# Power.net
KiCad netlist of a schematic drawn in Altium Designer
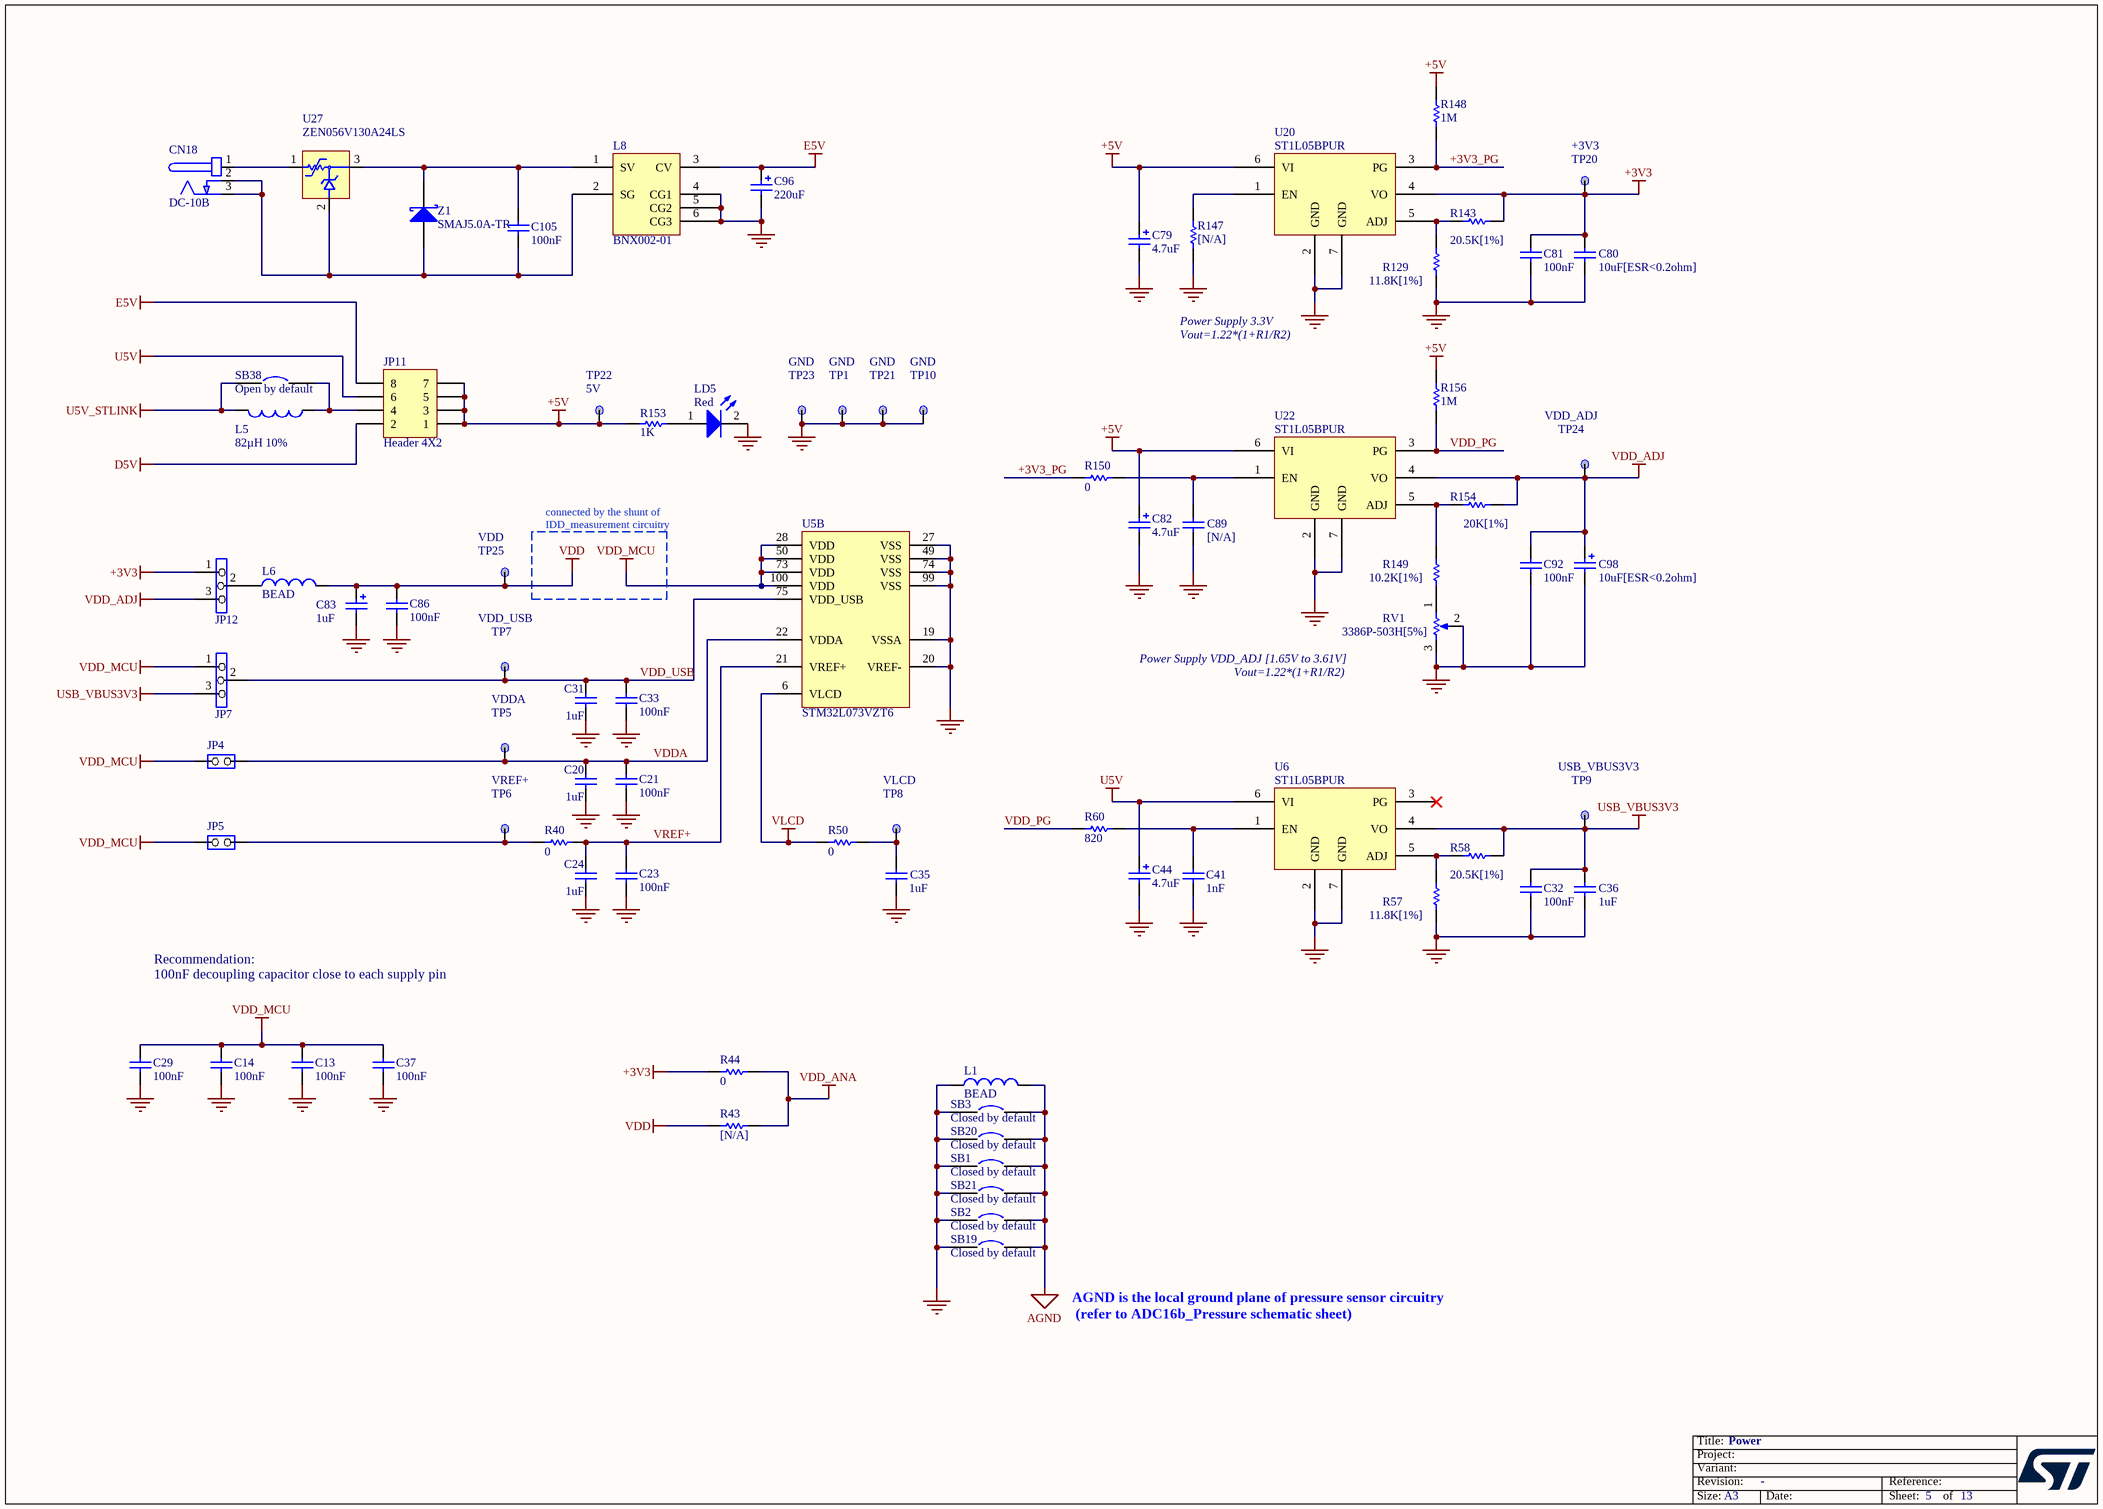
[diagram p0: Power.SchDoc]

(export (version "E")
  (design (tool "Eeschema 10.0.6"))
  (components
    (comp (ref "C13")
      (value "100nF")
      (footprint "0402C")
      (description "Capacitor")
      (fields (field (name "PUBLISHER") "Altium Limited"))
      (libsource (lib "Miscellaneous Devices") (part "CAP"))
    )
    (comp (ref "C14")
      (value "100nF")
      (footprint "0402C")
      (description "Capacitor")
      (fields (field (name "PUBLISHER") "Altium Limited"))
      (libsource (lib "Miscellaneous Devices") (part "CAP"))
    )
    (comp (ref "C20")
      (value "1uF")
      (footprint "0603C")
      (description "Capacitor")
      (fields (field (name "PUBLISHER") "Altium Limited"))
      (libsource (lib "Miscellaneous Devices") (part "CAP"))
    )
    (comp (ref "C21")
      (value "100nF")
      (footprint "0402C")
      (description "Capacitor")
      (fields (field (name "PUBLISHER") "Altium Limited"))
      (libsource (lib "Miscellaneous Devices") (part "Cap"))
    )
    (comp (ref "C23")
      (value "100nF")
      (footprint "0402C")
      (description "Capacitor")
      (fields (field (name "PUBLISHER") "Altium Limited"))
      (libsource (lib "Miscellaneous Devices") (part "Cap"))
    )
    (comp (ref "C24")
      (value "1uF")
      (footprint "0603C")
      (description "Capacitor")
      (fields (field (name "PUBLISHER") "Altium Limited"))
      (libsource (lib "Miscellaneous Devices") (part "CAP"))
    )
    (comp (ref "C29")
      (value "100nF")
      (footprint "0402C")
      (description "Capacitor")
      (fields (field (name "PUBLISHER") "Altium Limited"))
      (libsource (lib "Miscellaneous Devices") (part "CAP"))
    )
    (comp (ref "C31")
      (value "1uF")
      (footprint "0603C")
      (description "Capacitor")
      (fields (field (name "PUBLISHER") "Altium Limited"))
      (libsource (lib "Miscellaneous Devices") (part "CAP"))
    )
    (comp (ref "C32")
      (value "100nF")
      (footprint "0402C")
      (description "Capacitor")
      (fields (field (name "PUBLISHER") "Altium Limited"))
      (libsource (lib "Miscellaneous Devices") (part "Cap"))
    )
    (comp (ref "C33")
      (value "100nF")
      (footprint "0402C")
      (description "Capacitor")
      (fields (field (name "PUBLISHER") "Altium Limited"))
      (libsource (lib "Miscellaneous Devices") (part "Cap"))
    )
    (comp (ref "C35")
      (value "1uF")
      (footprint "0603C")
      (description "Capacitor")
      (fields (field (name "PUBLISHER") "Altium Limited"))
      (libsource (lib "Miscellaneous Devices") (part "CAP"))
    )
    (comp (ref "C36")
      (value "1uF")
      (footprint "0603C")
      (description "Capacitor")
      (fields (field (name "PUBLISHER") "Altium Limited"))
      (libsource (lib "Miscellaneous Devices") (part "Cap"))
    )
    (comp (ref "C37")
      (value "100nF")
      (footprint "0402C")
      (description "Capacitor")
      (fields (field (name "PUBLISHER") "Altium Limited"))
      (libsource (lib "Miscellaneous Devices") (part "CAP"))
    )
    (comp (ref "C41")
      (value "1nF")
      (footprint "0603C")
      (description "Capacitor")
      (fields (field (name "PUBLISHER") "Altium Limited"))
      (libsource (lib "Miscellaneous Devices") (part "Cap"))
    )
    (comp (ref "C44")
      (value "4.7uF")
      (footprint "TAN-A")
      (description "Polarized Capacitor (Radial)")
      (fields (field (name "PUBLISHER") "Altium Limited"))
      (libsource (lib "*") (part "Cap Pol1"))
    )
    (comp (ref "C79")
      (value "4.7uF")
      (footprint "TAN-A")
      (description "Polarized Capacitor (Radial)")
      (fields (field (name "PUBLISHER") "Altium Limited"))
      (libsource (lib "*") (part "Cap Pol1"))
    )
    (comp (ref "C80")
      (value "10uF[ESR<0.2ohm]")
      (footprint "0805C")
      (description "Capacitor")
      (fields (field (name "PUBLISHER") "Altium Limited"))
      (libsource (lib "Miscellaneous Devices") (part "Cap"))
    )
    (comp (ref "C81")
      (value "100nF")
      (footprint "0402C")
      (description "Capacitor")
      (fields (field (name "PUBLISHER") "Altium Limited"))
      (libsource (lib "Miscellaneous Devices") (part "Cap"))
    )
    (comp (ref "C82")
      (value "4.7uF")
      (footprint "TAN-A")
      (description "Polarized Capacitor (Radial)")
      (fields (field (name "PUBLISHER") "Altium Limited"))
      (libsource (lib "*") (part "Cap Pol1"))
    )
    (comp (ref "C83")
      (value "1uF")
      (footprint "TAN-A")
      (description "Polarized Capacitor")
      (fields (field (name "PUBLISHER") "Altium Limited"))
      (libsource (lib "Miscellaneous Devices") (part "Cap Pol1"))
    )
    (comp (ref "C86")
      (value "100nF")
      (footprint "0402C")
      (description "Capacitor")
      (fields (field (name "PUBLISHER") "Altium Limited"))
      (libsource (lib "Miscellaneous Devices") (part "Cap"))
    )
    (comp (ref "C89")
      (value "[N/A]")
      (footprint "0603C")
      (description "Capacitor")
      (fields (field (name "PUBLISHER") "Altium Limited"))
      (libsource (lib "Miscellaneous Devices") (part "cap"))
    )
    (comp (ref "C92")
      (value "100nF")
      (footprint "0402C")
      (description "Capacitor")
      (fields (field (name "PUBLISHER") "Altium Limited"))
      (libsource (lib "Miscellaneous Devices") (part "Cap"))
    )
    (comp (ref "C96")
      (value "220uF")
      (footprint "c310m-6")
      (description "Polarized Capacitor (Radial)")
      (fields (field (name "PUBLISHER") "Altium Limited"))
      (libsource (lib "Miscellaneous Devices") (part "Cap Pol1"))
    )
    (comp (ref "C98")
      (value "10uF[ESR<0.2ohm]")
      (footprint "0805C")
      (description "Polarized Capacitor (Radial)")
      (fields (field (name "PUBLISHER") "Altium Limited"))
      (libsource (lib "Miscellaneous Devices") (part "Cap Pol1"))
    )
    (comp (ref "C105")
      (value "100nF")
      (footprint "0402C")
      (description "Capacitor")
      (fields (field (name "PUBLISHER") "Altium Limited"))
      (libsource (lib "Miscellaneous Devices") (part "CAP"))
    )
    (comp (ref "CN18")
      (value "DC-10B")
      (footprint "PWR_JACK_DC10")
      (libsource (lib "STR910_SCHLIB") (part "PJ202A"))
    )
    (comp (ref "JP4") (value "~") (footprint "SIP2") (libsource (lib "*") (part "JP2")))
    (comp (ref "JP5") (value "~") (footprint "SIP2") (libsource (lib "*") (part "JP2")))
    (comp (ref "JP7") (value "~") (footprint "SIP3") (libsource (lib "STR910_SCHLIB") (part "Jumper3")))
    (comp (ref "JP11")
      (value "Header 4X2")
      (footprint "HDR_2X4_2R54")
      (description "Header, 4-Pin, Dual row")
      (fields (field (name "PUBLISHER") "Altium Limited"))
      (libsource (lib "Miscellaneous Connectors") (part "Header 4X2"))
    )
    (comp (ref "JP12") (value "~") (footprint "SIP3") (libsource (lib "STR910_SCHLIB") (part "Jumper3")))
    (comp (ref "L1")
      (value "BEAD")
      (footprint "0603L")
      (description "Bead,600R,350mA,0603")
      (fields (field (name "PUBLISHER") "Altium Limited"))
      (libsource (lib "Miscellaneous Devices") (part "Inductor"))
    )
    (comp (ref "L5")
      (value "82µH 10%")
      (footprint "LSM2_4R9X4R9_H4R1")
      (description "Power Inductor 82µH 0,65A")
      (libsource (lib "MCD_TOOLS") (part "Ind_82µH_0.65A_10%"))
    )
    (comp (ref "L6")
      (value "BEAD")
      (footprint "0603L")
      (description "Bead,600R,350mA,0603")
      (fields (field (name "PUBLISHER") "Altium Limited"))
      (libsource (lib "Miscellaneous Devices") (part "Inductor"))
    )
    (comp (ref "L8")
      (value "BNX002-01")
      (footprint "BNX001")
      (libsource (lib "STR910_SCHLIB") (part "BNX002"))
    )
    (comp (ref "LD5")
      (value "Red")
      (footprint "0603D")
      (description "Typical RED, GREEN, YELLOW, AMBER GaAs LED")
      (fields (field (name "PUBLISHER") "Altium Limited"))
      (libsource (lib "Miscellaneous Devices") (part "LED2"))
    )
    (comp (ref "R40")
      (value "0")
      (footprint "0603R")
      (description "Resistor")
      (fields (field (name "PUBLISHER") "Altium Limited"))
      (libsource (lib "Miscellaneous Devices") (part "Res1"))
    )
    (comp (ref "R43")
      (value "[N/A]")
      (footprint "0603R")
      (description "Resistor")
      (fields (field (name "PUBLISHER") "Altium Limited"))
      (libsource (lib "Miscellaneous Devices") (part "res1"))
    )
    (comp (ref "R44")
      (value "0")
      (footprint "0603R")
      (description "Resistor")
      (fields (field (name "PUBLISHER") "Altium Limited"))
      (libsource (lib "Miscellaneous Devices") (part "Res1"))
    )
    (comp (ref "R50")
      (value "0")
      (footprint "0603R")
      (description "Resistor")
      (fields (field (name "PUBLISHER") "Altium Limited"))
      (libsource (lib "Miscellaneous Devices") (part "Res1"))
    )
    (comp (ref "R57")
      (value "11.8K[1%]")
      (footprint "0603R")
      (description "Resistor")
      (fields (field (name "PUBLISHER") "Altium Limited"))
      (libsource (lib "Miscellaneous Devices") (part "Res1"))
    )
    (comp (ref "R58")
      (value "20.5K[1%]")
      (footprint "0603R")
      (description "Resistor")
      (fields (field (name "PUBLISHER") "Altium Limited"))
      (libsource (lib "Miscellaneous Devices") (part "Res1"))
    )
    (comp (ref "R60")
      (value "820")
      (footprint "0603R")
      (description "Resistor")
      (fields (field (name "PUBLISHER") "Altium Limited"))
      (libsource (lib "Miscellaneous Devices") (part "res1"))
    )
    (comp (ref "R129")
      (value "11.8K[1%]")
      (footprint "0603R")
      (description "Resistor")
      (fields (field (name "PUBLISHER") "Altium Limited"))
      (libsource (lib "Miscellaneous Devices") (part "Res1"))
    )
    (comp (ref "R143")
      (value "20.5K[1%]")
      (footprint "0603R")
      (description "Resistor")
      (fields (field (name "PUBLISHER") "Altium Limited"))
      (libsource (lib "Miscellaneous Devices") (part "Res1"))
    )
    (comp (ref "R147")
      (value "[N/A]")
      (footprint "0603R")
      (description "Resistor")
      (fields (field (name "PUBLISHER") "Altium Limited"))
      (libsource (lib "Miscellaneous Devices") (part "res1"))
    )
    (comp (ref "R148")
      (value "1M")
      (footprint "0603R")
      (description "Resistor")
      (fields (field (name "PUBLISHER") "Altium Limited"))
      (libsource (lib "Miscellaneous Devices") (part "res1"))
    )
    (comp (ref "R149")
      (value "10.2K[1%]")
      (footprint "0603R")
      (description "Resistor")
      (fields (field (name "PUBLISHER") "Altium Limited"))
      (libsource (lib "Miscellaneous Devices") (part "Res1"))
    )
    (comp (ref "R150")
      (value "0")
      (footprint "0603R")
      (description "Resistor")
      (fields (field (name "PUBLISHER") "Altium Limited"))
      (libsource (lib "Miscellaneous Devices") (part "res1"))
    )
    (comp (ref "R153")
      (value "1K")
      (footprint "0402R")
      (description "Resistor")
      (fields (field (name "PUBLISHER") "Altium Limited"))
      (libsource (lib "Miscellaneous Devices") (part "res1"))
    )
    (comp (ref "R154")
      (value "20K[1%]")
      (footprint "0603R")
      (description "Resistor")
      (fields (field (name "PUBLISHER") "Altium Limited"))
      (libsource (lib "Miscellaneous Devices") (part "Res1"))
    )
    (comp (ref "R156")
      (value "1M")
      (footprint "0603R")
      (description "Resistor")
      (fields (field (name "PUBLISHER") "Altium Limited"))
      (libsource (lib "Miscellaneous Devices") (part "res1"))
    )
    (comp (ref "RV1")
      (value "3386P-503H[5%]")
      (footprint "3386P")
      (description "Potentiometer 50K")
      (libsource (lib "STR910_SCHLIB") (part "RV"))
    )
    (comp (ref "SB1")
      (value "Closed by default")
      (footprint "SB_0603")
      (description "Circuit Breaker")
      (fields (field (name "PUBLISHER") "Altium Limited"))
      (libsource (lib "Miscellaneous Devices") (part "Circuit Breaker"))
    )
    (comp (ref "SB2")
      (value "Closed by default")
      (footprint "SB_0603")
      (description "Circuit Breaker")
      (fields (field (name "PUBLISHER") "Altium Limited"))
      (libsource (lib "Miscellaneous Devices") (part "Circuit Breaker"))
    )
    (comp (ref "SB3")
      (value "Closed by default")
      (footprint "SB_0603")
      (description "Circuit Breaker")
      (fields (field (name "PUBLISHER") "Altium Limited"))
      (libsource (lib "Miscellaneous Devices") (part "Circuit Breaker"))
    )
    (comp (ref "SB19")
      (value "Closed by default")
      (footprint "SB_0603")
      (description "Circuit Breaker")
      (fields (field (name "PUBLISHER") "Altium Limited"))
      (libsource (lib "Miscellaneous Devices") (part "Circuit Breaker"))
    )
    (comp (ref "SB20")
      (value "Closed by default")
      (footprint "SB_0603")
      (description "Circuit Breaker")
      (fields (field (name "PUBLISHER") "Altium Limited"))
      (libsource (lib "Miscellaneous Devices") (part "Circuit Breaker"))
    )
    (comp (ref "SB21")
      (value "Closed by default")
      (footprint "SB_0603")
      (description "Circuit Breaker")
      (fields (field (name "PUBLISHER") "Altium Limited"))
      (libsource (lib "Miscellaneous Devices") (part "Circuit Breaker"))
    )
    (comp (ref "SB38")
      (value "Open by default")
      (footprint "SB_0603")
      (description "Circuit Breaker")
      (fields (field (name "PUBLISHER") "Altium Limited"))
      (libsource (lib "Miscellaneous Devices") (part "Circuit Breaker"))
    )
    (comp (ref "TP1")
      (value "TP")
      (footprint "TP")
      (fields (field (name "SILKSCREEN") "GND"))
      (libsource (lib "*") (part "TP"))
    )
    (comp (ref "TP5")
      (value "TP")
      (footprint "TP")
      (fields (field (name "SILKSCREEN") "VDDA"))
      (libsource (lib "*") (part "TP"))
    )
    (comp (ref "TP6")
      (value "TP")
      (footprint "TP")
      (fields (field (name "SILKSCREEN") "VREF+"))
      (libsource (lib "*") (part "TP"))
    )
    (comp (ref "TP7")
      (value "TP")
      (footprint "TP")
      (fields (field (name "SILKSCREEN") "VDD_USB"))
      (libsource (lib "*") (part "TP"))
    )
    (comp (ref "TP8")
      (value "TP")
      (footprint "TP")
      (fields (field (name "SILKSCREEN") "VLCD"))
      (libsource (lib "*") (part "TP"))
    )
    (comp (ref "TP9")
      (value "TP")
      (footprint "TP")
      (fields (field (name "SILKSCREEN") "USB_VBUS3V3"))
      (libsource (lib "*") (part "TP"))
    )
    (comp (ref "TP10")
      (value "TP")
      (footprint "TP")
      (fields (field (name "SILKSCREEN") "GND"))
      (libsource (lib "*") (part "TP"))
    )
    (comp (ref "TP20")
      (value "TP")
      (footprint "TP")
      (fields (field (name "SILKSCREEN") "+3V3"))
      (libsource (lib "*") (part "TP"))
    )
    (comp (ref "TP21")
      (value "TP")
      (footprint "TP")
      (fields (field (name "SILKSCREEN") "GND"))
      (libsource (lib "*") (part "TP"))
    )
    (comp (ref "TP22")
      (value "TP")
      (footprint "TP")
      (fields (field (name "SILKSCREEN") "5V"))
      (libsource (lib "*") (part "TP"))
    )
    (comp (ref "TP23")
      (value "TP")
      (footprint "TP")
      (fields (field (name "SILKSCREEN") "GND"))
      (libsource (lib "*") (part "TP"))
    )
    (comp (ref "TP24")
      (value "TP")
      (footprint "TP")
      (fields (field (name "SILKSCREEN") "VDD_ADJ"))
      (libsource (lib "*") (part "TP"))
    )
    (comp (ref "TP25")
      (value "TP")
      (footprint "TP")
      (fields (field (name "SILKSCREEN") "VDD"))
      (libsource (lib "*") (part "TP"))
    )
    (comp (ref "U5")
      (value "STM32L073VZT6")
      (footprint "IC149_100_025_B5")
      (libsource (lib "Almos") (part "BigNemo"))
    )
    (comp (ref "U6")
      (value "ST1L05BPUR")
      (footprint "DFN6_0R95_3X3")
      (libsource (lib "MB1070") (part "ST1L05"))
    )
    (comp (ref "U20")
      (value "ST1L05BPUR")
      (footprint "DFN6_0R95_3X3")
      (libsource (lib "MB1070") (part "ST1L05"))
    )
    (comp (ref "U22")
      (value "ST1L05BPUR")
      (footprint "DFN6_0R95_3X3")
      (libsource (lib "MB1070") (part "ST1L05"))
    )
    (comp (ref "U27")
      (value "ZEN056V130A24LS")
      (footprint "TYCO_ZEN056V130A24LS")
      (libsource (lib "STR910_SCHLIB") (part "ZEN056V130A24LS"))
    )
    (comp (ref "Z1")
      (value "SMAJ5.0A-TR")
      (footprint "sma")
      (description "Schottky Diode")
      (fields (field (name "PUBLISHER") "Altium Limited"))
      (libsource (lib "Miscellaneous Devices") (part "D Schottky"))
    )
  )
  (nets
    (net (code "1") (name "+3V3") (class "Default")
      (node (ref "C80") (pin "1") (pinfunction "1_1") (pintype "passive"))
      (node (ref "C81") (pin "1") (pinfunction "1_1") (pintype "passive"))
      (node (ref "JP12") (pin "1") (pintype "passive"))
      (node (ref "R143") (pin "1") (pinfunction "1_1") (pintype "passive"))
      (node (ref "R44") (pin "1") (pinfunction "1_1") (pintype "passive"))
      (node (ref "TP20") (pin "1") (pinfunction "1_1") (pintype "passive"))
      (node (ref "U20") (pin "4") (pinfunction "VO_4") (pintype "passive"))
    )
    (net (code "2") (name "+5V") (class "Default")
      (node (ref "C79") (pin "1") (pinfunction "1_1") (pintype "passive"))
      (node (ref "C82") (pin "1") (pinfunction "1_1") (pintype "passive"))
      (node (ref "JP11") (pin "1") (pinfunction "1_1") (pintype "passive"))
      (node (ref "JP11") (pin "3") (pinfunction "3_3") (pintype "passive"))
      (node (ref "JP11") (pin "5") (pinfunction "5_5") (pintype "passive"))
      (node (ref "JP11") (pin "7") (pinfunction "7_7") (pintype "passive"))
      (node (ref "R148") (pin "1") (pinfunction "1_1") (pintype "passive"))
      (node (ref "R153") (pin "2") (pinfunction "2_2") (pintype "passive"))
      (node (ref "R156") (pin "1") (pinfunction "1_1") (pintype "passive"))
      (node (ref "TP22") (pin "1") (pinfunction "1_1") (pintype "passive"))
      (node (ref "U20") (pin "6") (pinfunction "VI_6") (pintype "passive"))
      (node (ref "U22") (pin "6") (pinfunction "VI_6") (pintype "passive"))
    )
    (net (code "3") (name "/+3V3_PG") (class "Default")
      (node (ref "R148") (pin "2") (pinfunction "2_2") (pintype "passive"))
      (node (ref "R150") (pin "1") (pinfunction "1_1") (pintype "passive"))
      (node (ref "U20") (pin "3") (pinfunction "PG_3") (pintype "passive"))
    )
    (net (code "4") (name "/VDDA") (class "Default")
      (node (ref "C20") (pin "1") (pinfunction "1_1") (pintype "passive"))
      (node (ref "C21") (pin "2") (pinfunction "2_2") (pintype "passive"))
      (node (ref "JP4") (pin "2") (pinfunction "NO_2") (pintype "passive"))
      (node (ref "TP5") (pin "1") (pinfunction "1_1") (pintype "passive"))
      (node (ref "U5") (pin "22") (pinfunction "VDDA_22") (pintype "passive"))
    )
    (net (code "5") (name "/VDD_PG") (class "Default")
      (node (ref "R156") (pin "2") (pinfunction "2_2") (pintype "passive"))
      (node (ref "R60") (pin "1") (pinfunction "1_1") (pintype "passive"))
      (node (ref "U22") (pin "3") (pinfunction "PG_3") (pintype "passive"))
    )
    (net (code "6") (name "/VDD_USB") (class "Default")
      (node (ref "C31") (pin "1") (pinfunction "1_1") (pintype "passive"))
      (node (ref "C33") (pin "2") (pinfunction "2_2") (pintype "passive"))
      (node (ref "JP7") (pin "2") (pintype "passive"))
      (node (ref "TP7") (pin "1") (pinfunction "1_1") (pintype "passive"))
      (node (ref "U5") (pin "75") (pinfunction "VDD_USB_75") (pintype "passive"))
    )
    (net (code "7") (name "/VREF+") (class "Default")
      (node (ref "C23") (pin "2") (pinfunction "2_2") (pintype "passive"))
      (node (ref "C24") (pin "1") (pinfunction "1_1") (pintype "passive"))
      (node (ref "R40") (pin "2") (pinfunction "2_2") (pintype "passive"))
      (node (ref "U5") (pin "21") (pinfunction "VREF+_21") (pintype "passive"))
    )
    (net (code "8") (name "AGND") (class "Default")
      (node (ref "L1") (pin "2") (pinfunction "2_2") (pintype "passive"))
      (node (ref "SB1") (pin "2") (pinfunction "2_2") (pintype "passive"))
      (node (ref "SB19") (pin "2") (pinfunction "2_2") (pintype "passive"))
      (node (ref "SB2") (pin "2") (pinfunction "2_2") (pintype "passive"))
      (node (ref "SB20") (pin "2") (pinfunction "2_2") (pintype "passive"))
      (node (ref "SB21") (pin "2") (pinfunction "2_2") (pintype "passive"))
      (node (ref "SB3") (pin "2") (pinfunction "2_2") (pintype "passive"))
    )
    (net (code "9") (name "D5V") (class "Default")
      (node (ref "JP11") (pin "2") (pinfunction "2_2") (pintype "passive"))
    )
    (net (code "10") (name "E5V") (class "Default")
      (node (ref "C96") (pin "1") (pinfunction "1_1") (pintype "passive"))
      (node (ref "JP11") (pin "8") (pinfunction "8_8") (pintype "passive"))
      (node (ref "L8") (pin "3") (pinfunction "CV_3") (pintype "passive"))
    )
    (net (code "11") (name "GND") (class "Default")
      (node (ref "C13") (pin "1") (pinfunction "1_1") (pintype "passive"))
      (node (ref "C14") (pin "1") (pinfunction "1_1") (pintype "passive"))
      (node (ref "C20") (pin "2") (pinfunction "2_2") (pintype "passive"))
      (node (ref "C21") (pin "1") (pinfunction "1_1") (pintype "passive"))
      (node (ref "C23") (pin "1") (pinfunction "1_1") (pintype "passive"))
      (node (ref "C24") (pin "2") (pinfunction "2_2") (pintype "passive"))
      (node (ref "C29") (pin "1") (pinfunction "1_1") (pintype "passive"))
      (node (ref "C31") (pin "2") (pinfunction "2_2") (pintype "passive"))
      (node (ref "C32") (pin "2") (pinfunction "2_2") (pintype "passive"))
      (node (ref "C33") (pin "1") (pinfunction "1_1") (pintype "passive"))
      (node (ref "C35") (pin "1") (pinfunction "1_1") (pintype "passive"))
      (node (ref "C36") (pin "2") (pinfunction "2_2") (pintype "passive"))
      (node (ref "C37") (pin "1") (pinfunction "1_1") (pintype "passive"))
      (node (ref "C41") (pin "2") (pinfunction "2_2") (pintype "passive"))
      (node (ref "C44") (pin "2") (pinfunction "2_2") (pintype "passive"))
      (node (ref "C79") (pin "2") (pinfunction "2_2") (pintype "passive"))
      (node (ref "C80") (pin "2") (pinfunction "2_2") (pintype "passive"))
      (node (ref "C81") (pin "2") (pinfunction "2_2") (pintype "passive"))
      (node (ref "C82") (pin "2") (pinfunction "2_2") (pintype "passive"))
      (node (ref "C83") (pin "2") (pinfunction "2_2") (pintype "passive"))
      (node (ref "C86") (pin "1") (pinfunction "1_1") (pintype "passive"))
      (node (ref "C89") (pin "1") (pinfunction "1_1") (pintype "passive"))
      (node (ref "C92") (pin "2") (pinfunction "2_2") (pintype "passive"))
      (node (ref "C96") (pin "2") (pinfunction "2_2") (pintype "passive"))
      (node (ref "C98") (pin "2") (pinfunction "2_2") (pintype "passive"))
      (node (ref "L1") (pin "1") (pinfunction "1_1") (pintype "passive"))
      (node (ref "L8") (pin "4") (pinfunction "CG1_4") (pintype "passive"))
      (node (ref "L8") (pin "5") (pinfunction "CG2_5") (pintype "passive"))
      (node (ref "L8") (pin "6") (pinfunction "CG3_6") (pintype "passive"))
      (node (ref "LD5") (pin "2") (pinfunction "K_2") (pintype "passive"))
      (node (ref "R129") (pin "2") (pinfunction "2_2") (pintype "passive"))
      (node (ref "R147") (pin "2") (pinfunction "2_2") (pintype "passive"))
      (node (ref "R57") (pin "2") (pinfunction "2_2") (pintype "passive"))
      (node (ref "RV1") (pin "2") (pinfunction "TAP_2") (pintype "passive"))
      (node (ref "RV1") (pin "3") (pinfunction "TOP_3") (pintype "passive"))
      (node (ref "SB1") (pin "1") (pinfunction "1_1") (pintype "passive"))
      (node (ref "SB19") (pin "1") (pinfunction "1_1") (pintype "passive"))
      (node (ref "SB2") (pin "1") (pinfunction "1_1") (pintype "passive"))
      (node (ref "SB20") (pin "1") (pinfunction "1_1") (pintype "passive"))
      (node (ref "SB21") (pin "1") (pinfunction "1_1") (pintype "passive"))
      (node (ref "SB3") (pin "1") (pinfunction "1_1") (pintype "passive"))
      (node (ref "TP1") (pin "1") (pinfunction "1_1") (pintype "passive"))
      (node (ref "TP10") (pin "1") (pinfunction "1_1") (pintype "passive"))
      (node (ref "TP21") (pin "1") (pinfunction "1_1") (pintype "passive"))
      (node (ref "TP23") (pin "1") (pinfunction "1_1") (pintype "passive"))
      (node (ref "U20") (pin "2") (pinfunction "GND_2") (pintype "passive"))
      (node (ref "U20") (pin "7") (pinfunction "GND_7") (pintype "passive"))
      (node (ref "U22") (pin "2") (pinfunction "GND_2") (pintype "passive"))
      (node (ref "U22") (pin "7") (pinfunction "GND_7") (pintype "passive"))
      (node (ref "U5") (pin "19") (pinfunction "VSSA_19") (pintype "passive"))
      (node (ref "U5") (pin "20") (pinfunction "VREF-_20") (pintype "passive"))
      (node (ref "U5") (pin "27") (pinfunction "VSS_27") (pintype "passive"))
      (node (ref "U5") (pin "49") (pinfunction "VSS_49") (pintype "passive"))
      (node (ref "U5") (pin "74") (pinfunction "VSS_74") (pintype "passive"))
      (node (ref "U5") (pin "99") (pinfunction "VSS_99") (pintype "passive"))
      (node (ref "U6") (pin "2") (pinfunction "GND_2") (pintype "passive"))
      (node (ref "U6") (pin "7") (pinfunction "GND_7") (pintype "passive"))
    )
    (net (code "12") (name "Net-(C35-Pad2)") (class "Default")
      (node (ref "C35") (pin "2") (pinfunction "2_2") (pintype "passive"))
      (node (ref "R50") (pin "2") (pinfunction "2_2") (pintype "passive"))
      (node (ref "TP8") (pin "1") (pinfunction "1_1") (pintype "passive"))
    )
    (net (code "13") (name "Net-(CN18-+)") (class "Default")
      (node (ref "CN18") (pin "1") (pinfunction "+_1") (pintype "passive"))
      (node (ref "U27") (pin "1") (pintype "passive"))
    )
    (net (code "14") (name "Net-(JP5-NO)") (class "Default")
      (node (ref "JP5") (pin "2") (pinfunction "NO_2") (pintype "passive"))
      (node (ref "R40") (pin "1") (pinfunction "1_1") (pintype "passive"))
      (node (ref "TP6") (pin "1") (pinfunction "1_1") (pintype "passive"))
    )
    (net (code "15") (name "Net-(JP11-Pad4)") (class "Default")
      (node (ref "JP11") (pin "4") (pinfunction "4_4") (pintype "passive"))
      (node (ref "L5") (pin "1") (pinfunction "1_1") (pintype "passive"))
      (node (ref "SB38") (pin "2") (pinfunction "2_2") (pintype "passive"))
    )
    (net (code "16") (name "Net-(JP12-Pad2)") (class "Default")
      (node (ref "JP12") (pin "2") (pintype "passive"))
      (node (ref "L6") (pin "1") (pinfunction "1_1") (pintype "passive"))
    )
    (net (code "17") (name "Net-(L8-SG)") (class "Default")
      (node (ref "C105") (pin "2") (pinfunction "2_2") (pintype "passive"))
      (node (ref "CN18") (pin "2") (pinfunction "GND_2") (pintype "passive"))
      (node (ref "CN18") (pin "3") (pinfunction "GND_3") (pintype "passive"))
      (node (ref "L8") (pin "2") (pinfunction "SG_2") (pintype "passive"))
      (node (ref "U27") (pin "2") (pintype "passive"))
      (node (ref "Z1") (pin "1") (pinfunction "A_1") (pintype "passive"))
    )
    (net (code "18") (name "Net-(L8-SV)") (class "Default")
      (node (ref "C105") (pin "1") (pinfunction "1_1") (pintype "passive"))
      (node (ref "L8") (pin "1") (pinfunction "SV_1") (pintype "passive"))
      (node (ref "U27") (pin "3") (pintype "passive"))
      (node (ref "Z1") (pin "2") (pinfunction "K_2") (pintype "passive"))
    )
    (net (code "19") (name "Net-(LD5-A)") (class "Default")
      (node (ref "LD5") (pin "1") (pinfunction "A_1") (pintype "passive"))
      (node (ref "R153") (pin "1") (pinfunction "1_1") (pintype "passive"))
    )
    (net (code "20") (name "Net-(RV1-BOT)") (class "Default")
      (node (ref "R149") (pin "2") (pinfunction "2_2") (pintype "passive"))
      (node (ref "RV1") (pin "1") (pinfunction "BOT_1") (pintype "passive"))
    )
    (net (code "21") (name "Net-(U6-ADJ)") (class "Default")
      (node (ref "R57") (pin "1") (pinfunction "1_1") (pintype "passive"))
      (node (ref "R58") (pin "2") (pinfunction "2_2") (pintype "passive"))
      (node (ref "U6") (pin "5") (pinfunction "ADJ_5") (pintype "passive"))
    )
    (net (code "22") (name "Net-(U6-EN)") (class "Default")
      (node (ref "C41") (pin "1") (pinfunction "1_1") (pintype "passive"))
      (node (ref "R60") (pin "2") (pinfunction "2_2") (pintype "passive"))
      (node (ref "U6") (pin "1") (pinfunction "EN_1") (pintype "passive"))
    )
    (net (code "23") (name "Net-(U20-ADJ)") (class "Default")
      (node (ref "R129") (pin "1") (pinfunction "1_1") (pintype "passive"))
      (node (ref "R143") (pin "2") (pinfunction "2_2") (pintype "passive"))
      (node (ref "U20") (pin "5") (pinfunction "ADJ_5") (pintype "passive"))
    )
    (net (code "24") (name "Net-(U20-EN)") (class "Default")
      (node (ref "R147") (pin "1") (pinfunction "1_1") (pintype "passive"))
      (node (ref "U20") (pin "1") (pinfunction "EN_1") (pintype "passive"))
    )
    (net (code "25") (name "Net-(U22-ADJ)") (class "Default")
      (node (ref "R149") (pin "1") (pinfunction "1_1") (pintype "passive"))
      (node (ref "R154") (pin "2") (pinfunction "2_2") (pintype "passive"))
      (node (ref "U22") (pin "5") (pinfunction "ADJ_5") (pintype "passive"))
    )
    (net (code "26") (name "Net-(U22-EN)") (class "Default")
      (node (ref "C89") (pin "2") (pinfunction "2_2") (pintype "passive"))
      (node (ref "R150") (pin "2") (pinfunction "2_2") (pintype "passive"))
      (node (ref "U22") (pin "1") (pinfunction "EN_1") (pintype "passive"))
    )
    (net (code "27") (name "U5V") (class "Default")
      (node (ref "C44") (pin "1") (pinfunction "1_1") (pintype "passive"))
      (node (ref "JP11") (pin "6") (pinfunction "6_6") (pintype "passive"))
      (node (ref "U6") (pin "6") (pinfunction "VI_6") (pintype "passive"))
    )
    (net (code "28") (name "U5V_STLINK") (class "Default")
      (node (ref "L5") (pin "2") (pinfunction "2_2") (pintype "passive"))
      (node (ref "SB38") (pin "1") (pinfunction "1_1") (pintype "passive"))
    )
    (net (code "29") (name "USB_VBUS3V3") (class "Default")
      (node (ref "C32") (pin "1") (pinfunction "1_1") (pintype "passive"))
      (node (ref "C36") (pin "1") (pinfunction "1_1") (pintype "passive"))
      (node (ref "JP7") (pin "3") (pintype "passive"))
      (node (ref "R58") (pin "1") (pinfunction "1_1") (pintype "passive"))
      (node (ref "TP9") (pin "1") (pinfunction "1_1") (pintype "passive"))
      (node (ref "U6") (pin "4") (pinfunction "VO_4") (pintype "passive"))
    )
    (net (code "30") (name "VDD") (class "Default")
      (node (ref "C83") (pin "1") (pinfunction "1_1") (pintype "passive"))
      (node (ref "C86") (pin "2") (pinfunction "2_2") (pintype "passive"))
      (node (ref "L6") (pin "2") (pinfunction "2_2") (pintype "passive"))
      (node (ref "R43") (pin "1") (pinfunction "1_1") (pintype "passive"))
      (node (ref "TP25") (pin "1") (pinfunction "1_1") (pintype "passive"))
    )
    (net (code "31") (name "VDD_ADJ") (class "Default")
      (node (ref "C92") (pin "1") (pinfunction "1_1") (pintype "passive"))
      (node (ref "C98") (pin "1") (pinfunction "1_1") (pintype "passive"))
      (node (ref "JP12") (pin "3") (pintype "passive"))
      (node (ref "R154") (pin "1") (pinfunction "1_1") (pintype "passive"))
      (node (ref "TP24") (pin "1") (pinfunction "1_1") (pintype "passive"))
      (node (ref "U22") (pin "4") (pinfunction "VO_4") (pintype "passive"))
    )
    (net (code "32") (name "VDD_ANA") (class "Default")
      (node (ref "R43") (pin "2") (pinfunction "2_2") (pintype "passive"))
      (node (ref "R44") (pin "2") (pinfunction "2_2") (pintype "passive"))
    )
    (net (code "33") (name "VDD_MCU") (class "Default")
      (node (ref "C13") (pin "2") (pinfunction "2_2") (pintype "passive"))
      (node (ref "C14") (pin "2") (pinfunction "2_2") (pintype "passive"))
      (node (ref "C29") (pin "2") (pinfunction "2_2") (pintype "passive"))
      (node (ref "C37") (pin "2") (pinfunction "2_2") (pintype "passive"))
      (node (ref "JP4") (pin "1") (pinfunction "COMMON_1") (pintype "passive"))
      (node (ref "JP5") (pin "1") (pinfunction "COMMON_1") (pintype "passive"))
      (node (ref "JP7") (pin "1") (pintype "passive"))
      (node (ref "U5") (pin "100") (pinfunction "VDD_100") (pintype "passive"))
      (node (ref "U5") (pin "28") (pinfunction "VDD_28") (pintype "passive"))
      (node (ref "U5") (pin "50") (pinfunction "VDD_50") (pintype "passive"))
      (node (ref "U5") (pin "73") (pinfunction "VDD_73") (pintype "passive"))
    )
    (net (code "34") (name "VLCD") (class "Default")
      (node (ref "R50") (pin "1") (pinfunction "1_1") (pintype "passive"))
      (node (ref "U5") (pin "6") (pinfunction "VLCD_6") (pintype "passive"))
    )
    (net (code "35") (name "unconnected-(U6-PG-Pad3)") (class "Default")
      (node (ref "U6") (pin "3") (pinfunction "PG_3") (pintype "passive+no_connect"))
    )
  )
)
